# TimerSwitch.net
KiCad netlist of a schematic drawn in Altium Designer
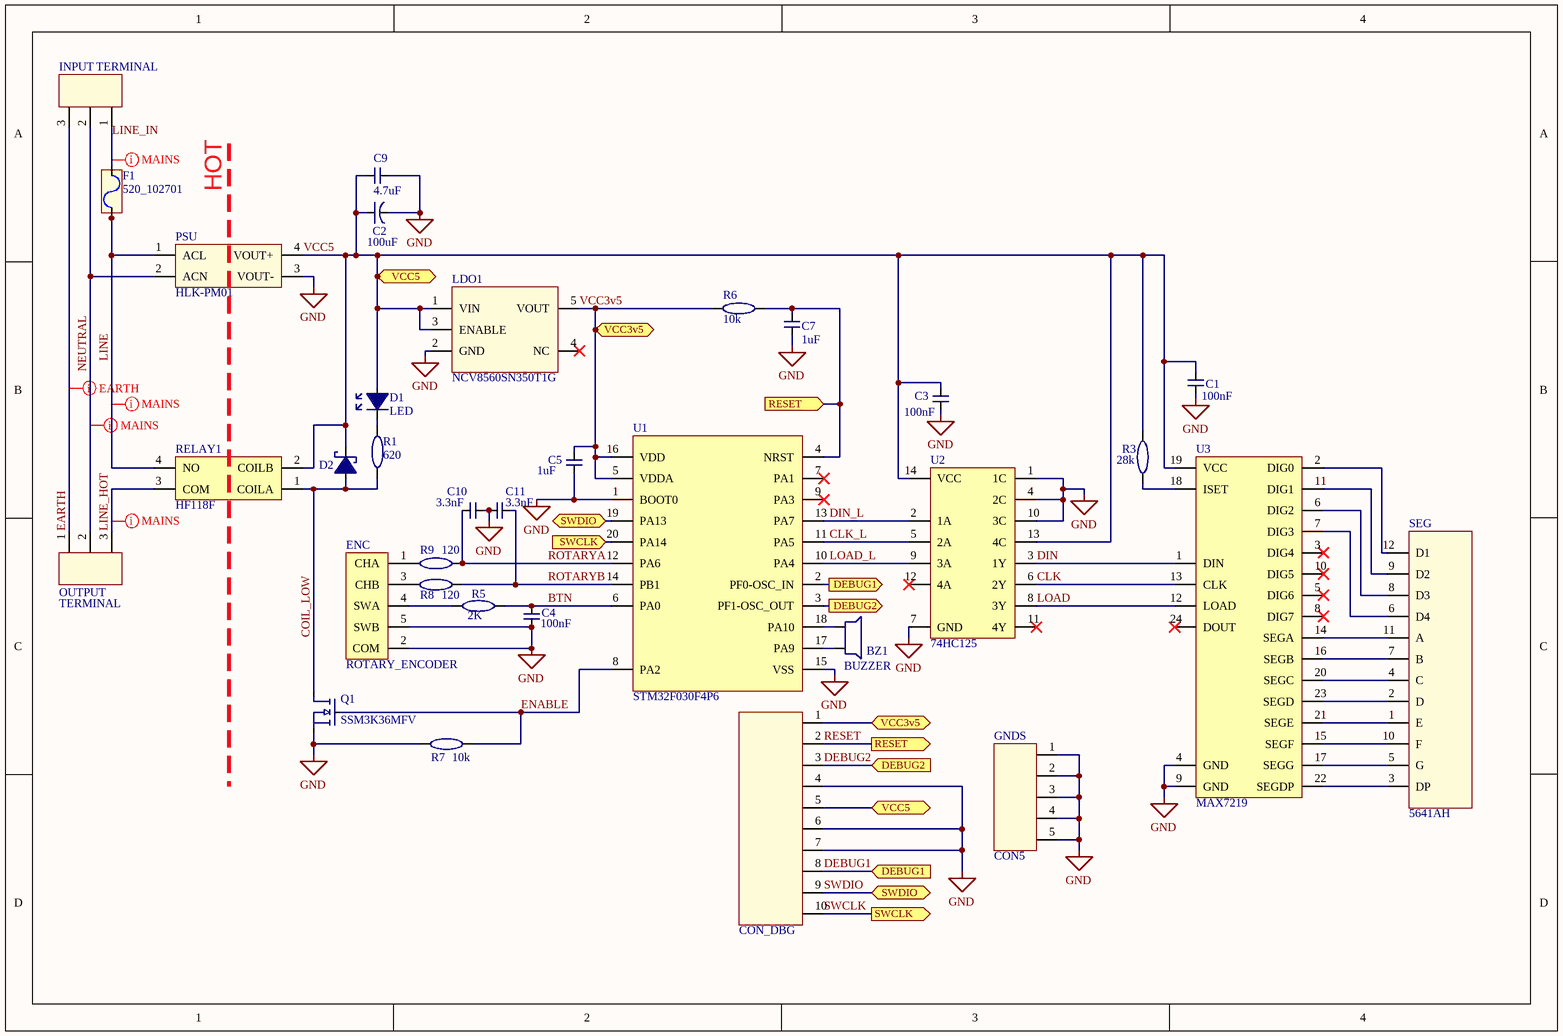
[diagram p0: TimerSwitch.SchDoc]

(export (version "E")
  (design (tool "Eeschema 10.0.6"))
  (components
    (comp (ref "BZ1")
      (value "BUZZER")
      (footprint "PIEZO_BUZZER")
      (libsource (lib "TimerSwitch") (part "BUZZER"))
    )
    (comp (ref "C1")
      (value "100nF")
      (footprint "CAPC1608X07L")
      (libsource (lib "TimerSwitch") (part "CAP_CERAMIC"))
    )
    (comp (ref "C2")
      (value "100uF")
      (footprint "CAPAE9585X105L")
      (libsource (lib "TimerSwitch") (part "CAP_ELECTROLYTIC"))
    )
    (comp (ref "C3")
      (value "100nF")
      (footprint "CAPC1608X07L")
      (libsource (lib "TimerSwitch") (part "CAP_CERAMIC"))
    )
    (comp (ref "C4")
      (value "100nF")
      (footprint "CAPC1608X07L")
      (libsource (lib "TimerSwitch") (part "CAP_CERAMIC"))
    )
    (comp (ref "C5")
      (value "1uF")
      (footprint "CAPC1608X07L")
      (libsource (lib "TimerSwitch") (part "CAP_CERAMIC"))
    )
    (comp (ref "C7")
      (value "1uF")
      (footprint "CAPC1608X07L")
      (libsource (lib "TimerSwitch") (part "CAP_CERAMIC"))
    )
    (comp (ref "C9")
      (value "4.7uF")
      (footprint "CAPC3216X07L")
      (description "Ceramic capacitor")
      (libsource (lib "TimerSwitch") (part "CAP_CERAMIC"))
    )
    (comp (ref "C10")
      (value "3.3nF")
      (footprint "CAPC1608X07L")
      (description "Ceramic capacitor")
      (libsource (lib "TimerSwitch") (part "CAP_CERAMIC"))
    )
    (comp (ref "C11")
      (value "3.3nF")
      (footprint "CAPC1608X07L")
      (description "Ceramic capacitor")
      (libsource (lib "TimerSwitch") (part "CAP_CERAMIC"))
    )
    (comp (ref "CON_DBG")
      (value "CON10")
      (footprint "CON10")
      (description "Debug connector")
      (libsource (lib "TimerSwitch") (part "CON10"))
    )
    (comp (ref "D1")
      (value "LED")
      (footprint "LED")
      (description "5mm through hole LED")
      (libsource (lib "TimerSwitch") (part "LED"))
    )
    (comp (ref "D2")
      (value "DSF05S30U")
      (footprint "SODFL250X100-2L")
      (description "Schottky Diode 20v 500mA")
      (libsource (lib "TimerSwitch") (part "DSF05S30U"))
    )
    (comp (ref "ENC")
      (value "ROTARY_ENCODER")
      (footprint "PEC12R-4XXXF-SXXXX_1")
      (description "Generic rotary encoder")
      (libsource (lib "TimerSwitch") (part "ROTARY_ENCODER"))
    )
    (comp (ref "F1")
      (value "520_102701")
      (footprint "5x20 FUSE")
      (description "5x20 5A fuse speed F")
      (libsource (lib "TimerSwitch") (part "520_102701"))
    )
    (comp (ref "GNDS") (value "CON5") (footprint "CON5") (libsource (lib "TimerSwitch") (part "CON5")))
    (comp (ref "INPUT")
      (value "TERMINAL")
      (footprint "TERMINAL_BLOCK")
      (description "3 way terminal block")
      (libsource (lib "") (part "TERMINAL_1"))
    )
    (comp (ref "LDO1")
      (value "NCV8560SN350T1G")
      (footprint "TSOP95P280X110-6L")
      (description "3.5V 150mA LDO")
      (libsource (lib "TimerSwitch") (part "NCV8560SN350T1G"))
    )
    (comp (ref "OUTPUT")
      (value "TERMINAL")
      (footprint "TERMINAL_BLOCK")
      (description "3 way terminal block")
      (libsource (lib "TimerSwitch") (part "TERMINAL"))
    )
    (comp (ref "PSU")
      (value "HLK-PM01")
      (footprint "HLK-PM01")
      (description "5V PSU 0.6A")
      (libsource (lib "TimerSwitch") (part "HLK-PM01"))
    )
    (comp (ref "Q1")
      (value "SSM3K36MFV")
      (footprint "SOT95P230X110-3L")
      (description "MOSFET N")
      (libsource (lib "TimerSwitch") (part "SSM3K36MFV"))
    )
    (comp (ref "R1")
      (value "620")
      (footprint "RESC1608X05L")
      (libsource (lib "TimerSwitch") (part "RESISTOR"))
    )
    (comp (ref "R3")
      (value "28k")
      (footprint "RESC1608X05L")
      (libsource (lib "TimerSwitch") (part "RESISTOR"))
    )
    (comp (ref "R5")
      (value "2K")
      (footprint "RESC1608X05L")
      (libsource (lib "TimerSwitch") (part "RESISTOR"))
    )
    (comp (ref "R6")
      (value "10k")
      (footprint "RESC1608X05L")
      (libsource (lib "TimerSwitch") (part "RESISTOR"))
    )
    (comp (ref "R7")
      (value "10k")
      (footprint "RESC1608X05L")
      (libsource (lib "TimerSwitch") (part "RESISTOR"))
    )
    (comp (ref "R8")
      (value "120")
      (footprint "RESC1608X05L")
      (description "Resistor 1%")
      (libsource (lib "TimerSwitch") (part "RESISTOR"))
    )
    (comp (ref "R9")
      (value "120")
      (footprint "RESC1608X05L")
      (description "Resistor 1%")
      (libsource (lib "TimerSwitch") (part "RESISTOR"))
    )
    (comp (ref "RELAY1")
      (value "HF118F")
      (footprint "G5RL-1-E-HR")
      (description "240V 10A Relay 5V")
      (libsource (lib "TimerSwitch") (part "HF118F"))
    )
    (comp (ref "SEG")
      (value "5641AH")
      (footprint "5641AH")
      (description "7+1 x 4 Segment display")
      (libsource (lib "TimerSwitch") (part "5641AH"))
    )
    (comp (ref "U1")
      (value "STM32F030F4P6")
      (footprint "TSOP65P630X120-20L")
      (description "Microcontroller 4KB RAM 16KB Flash")
      (libsource (lib "TimerSwitch") (part "STM32F030F4P6"))
    )
    (comp (ref "U2")
      (value "74HC125")
      (footprint "SOIC127P600X175-14L")
      (description "4 Channel level shifter")
      (libsource (lib "TimerSwitch") (part "74HC125"))
    )
    (comp (ref "U3")
      (value "MAX7219")
      (footprint "SOIC127P1030X265-24L")
      (description "7 Segment LED Driver")
      (libsource (lib "TimerSwitch") (part "MAX7219"))
    )
  )
  (nets
    (net (code "1") (name "/BTN") (class "Default")
      (node (ref "C4") (pin "2") (pinfunction "B_2") (pintype "passive"))
      (node (ref "R5") (pin "1") (pinfunction "A_1") (pintype "passive"))
      (node (ref "U1") (pin "6") (pinfunction "PA0_6") (pintype "passive"))
    )
    (net (code "2") (name "/CLK") (class "Default")
      (node (ref "U2") (pin "6") (pinfunction "2Y_6") (pintype "passive"))
      (node (ref "U3") (pin "13") (pinfunction "CLK_13") (pintype "passive"))
    )
    (net (code "3") (name "/CLK_L") (class "Default")
      (node (ref "U1") (pin "11") (pinfunction "PA5_11") (pintype "passive"))
      (node (ref "U2") (pin "5") (pinfunction "2A_5") (pintype "passive"))
    )
    (net (code "4") (name "/COIL_LOW") (class "Default")
      (node (ref "D2") (pin "1") (pinfunction "A_1") (pintype "passive"))
      (node (ref "Q1") (pin "3") (pinfunction "D_3") (pintype "passive"))
      (node (ref "R1") (pin "1") (pinfunction "A_1") (pintype "passive"))
      (node (ref "RELAY1") (pin "1") (pinfunction "COILA_1") (pintype "passive"))
    )
    (net (code "5") (name "/DEBUG1") (class "Default")
      (node (ref "CON_DBG") (pin "8") (pinfunction "8_8") (pintype "passive"))
      (node (ref "U1") (pin "2") (pinfunction "PF0-OSC_IN_2") (pintype "passive"))
    )
    (net (code "6") (name "/DEBUG2") (class "Default")
      (node (ref "CON_DBG") (pin "3") (pintype "passive"))
      (node (ref "U1") (pin "3") (pinfunction "PF1-OSC_OUT_3") (pintype "passive"))
    )
    (net (code "7") (name "/DIN") (class "Default")
      (node (ref "U2") (pin "3") (pinfunction "1Y_3") (pintype "passive"))
      (node (ref "U3") (pin "1") (pinfunction "DIN_1") (pintype "passive"))
    )
    (net (code "8") (name "/DIN_L") (class "Default")
      (node (ref "U1") (pin "13") (pinfunction "PA7_13") (pintype "passive"))
      (node (ref "U2") (pin "2") (pinfunction "1A_2") (pintype "passive"))
    )
    (net (code "9") (name "/EARTH") (class "Default")
      (node (ref "INPUT") (pin "3") (pinfunction "3_3") (pintype "passive"))
      (node (ref "OUTPUT") (pin "1") (pinfunction "1_1") (pintype "passive"))
    )
    (net (code "10") (name "/ENABLE") (class "Default")
      (node (ref "Q1") (pin "1") (pinfunction "G_1") (pintype "passive"))
      (node (ref "R7") (pin "2") (pinfunction "B_2") (pintype "passive"))
      (node (ref "U1") (pin "8") (pinfunction "PA2_8") (pintype "passive"))
    )
    (net (code "11") (name "/LINE") (class "Default")
      (node (ref "F1") (pin "2") (pinfunction "2_2") (pintype "passive"))
      (node (ref "PSU") (pin "1") (pinfunction "ACL_1") (pintype "passive"))
      (node (ref "RELAY1") (pin "4") (pinfunction "NO_4") (pintype "passive"))
    )
    (net (code "12") (name "/LINE_HOT") (class "Default")
      (node (ref "OUTPUT") (pin "3") (pinfunction "3_3") (pintype "passive"))
      (node (ref "RELAY1") (pin "3") (pinfunction "COM_3") (pintype "passive"))
    )
    (net (code "13") (name "/LINE_IN") (class "Default")
      (node (ref "F1") (pin "1") (pinfunction "1_1") (pintype "passive"))
      (node (ref "INPUT") (pin "1") (pinfunction "1_1") (pintype "passive"))
    )
    (net (code "14") (name "/LOAD") (class "Default")
      (node (ref "U2") (pin "8") (pinfunction "3Y_8") (pintype "passive"))
      (node (ref "U3") (pin "12") (pinfunction "LOAD_12") (pintype "passive"))
    )
    (net (code "15") (name "/LOAD_L") (class "Default")
      (node (ref "U1") (pin "10") (pinfunction "PA4_10") (pintype "passive"))
      (node (ref "U2") (pin "9") (pinfunction "3A_9") (pintype "passive"))
    )
    (net (code "16") (name "/NEUTRAL") (class "Default")
      (node (ref "INPUT") (pin "2") (pinfunction "2_2") (pintype "passive"))
      (node (ref "OUTPUT") (pin "2") (pinfunction "2_2") (pintype "passive"))
      (node (ref "PSU") (pin "2") (pinfunction "ACN_2") (pintype "passive"))
    )
    (net (code "17") (name "/RESET") (class "Default")
      (node (ref "C7") (pin "2") (pinfunction "B_2") (pintype "passive"))
      (node (ref "CON_DBG") (pin "2") (pintype "passive"))
      (node (ref "R6") (pin "1") (pinfunction "A_1") (pintype "passive"))
      (node (ref "U1") (pin "4") (pinfunction "NRST_4") (pintype "passive"))
    )
    (net (code "18") (name "/ROTARYA") (class "Default")
      (node (ref "C10") (pin "1") (pinfunction "A_1") (pintype "passive"))
      (node (ref "R9") (pin "2") (pinfunction "B_2") (pintype "passive"))
      (node (ref "U1") (pin "12") (pinfunction "PA6_12") (pintype "passive"))
    )
    (net (code "19") (name "/ROTARYB") (class "Default")
      (node (ref "C11") (pin "2") (pinfunction "B_2") (pintype "passive"))
      (node (ref "R8") (pin "2") (pinfunction "B_2") (pintype "passive"))
      (node (ref "U1") (pin "14") (pinfunction "PB1_14") (pintype "passive"))
    )
    (net (code "20") (name "/SWCLK") (class "Default")
      (node (ref "CON_DBG") (pin "10") (pinfunction "10_10") (pintype "passive"))
      (node (ref "U1") (pin "20") (pinfunction "PA14_20") (pintype "passive"))
    )
    (net (code "21") (name "/SWDIO") (class "Default")
      (node (ref "CON_DBG") (pin "9") (pinfunction "9_9") (pintype "passive"))
      (node (ref "U1") (pin "19") (pinfunction "PA13_19") (pintype "passive"))
    )
    (net (code "22") (name "/VCC3v5") (class "Default")
      (node (ref "C5") (pin "1") (pinfunction "A_1") (pintype "passive"))
      (node (ref "CON_DBG") (pin "1") (pintype "passive"))
      (node (ref "LDO1") (pin "5") (pinfunction "VOUT_5") (pintype "passive"))
      (node (ref "R6") (pin "2") (pinfunction "B_2") (pintype "passive"))
      (node (ref "U1") (pin "16") (pinfunction "VDD_16") (pintype "passive"))
      (node (ref "U1") (pin "5") (pinfunction "VDDA_5") (pintype "passive"))
    )
    (net (code "23") (name "/VCC5") (class "Default")
      (node (ref "C1") (pin "2") (pinfunction "B_2") (pintype "passive"))
      (node (ref "C2") (pin "1") (pinfunction "A_1") (pintype "passive"))
      (node (ref "C3") (pin "2") (pinfunction "B_2") (pintype "passive"))
      (node (ref "C9") (pin "1") (pinfunction "A_1") (pintype "passive"))
      (node (ref "CON_DBG") (pin "5") (pintype "passive"))
      (node (ref "D1") (pin "1") (pinfunction "A_1") (pintype "passive"))
      (node (ref "D2") (pin "2") (pinfunction "C_2") (pintype "passive"))
      (node (ref "LDO1") (pin "1") (pinfunction "VIN_1") (pintype "passive"))
      (node (ref "LDO1") (pin "3") (pinfunction "ENABLE_3") (pintype "passive"))
      (node (ref "PSU") (pin "4") (pinfunction "VOUT+_4") (pintype "passive"))
      (node (ref "R3") (pin "2") (pinfunction "B_2") (pintype "passive"))
      (node (ref "RELAY1") (pin "2") (pinfunction "COILB_2") (pintype "passive"))
      (node (ref "U2") (pin "13") (pinfunction "4C_13") (pintype "passive"))
      (node (ref "U2") (pin "14") (pinfunction "VCC_14") (pintype "passive"))
      (node (ref "U3") (pin "19") (pinfunction "VCC_19") (pintype "passive"))
    )
    (net (code "24") (name "GND") (class "Default")
      (node (ref "C1") (pin "1") (pinfunction "A_1") (pintype "passive"))
      (node (ref "C10") (pin "2") (pinfunction "B_2") (pintype "passive"))
      (node (ref "C11") (pin "1") (pinfunction "A_1") (pintype "passive"))
      (node (ref "C2") (pin "2") (pinfunction "C_2") (pintype "passive"))
      (node (ref "C3") (pin "1") (pinfunction "A_1") (pintype "passive"))
      (node (ref "C4") (pin "1") (pinfunction "A_1") (pintype "passive"))
      (node (ref "C5") (pin "2") (pinfunction "B_2") (pintype "passive"))
      (node (ref "C7") (pin "1") (pinfunction "A_1") (pintype "passive"))
      (node (ref "C9") (pin "2") (pinfunction "B_2") (pintype "passive"))
      (node (ref "CON_DBG") (pin "4") (pintype "passive"))
      (node (ref "CON_DBG") (pin "6") (pintype "passive"))
      (node (ref "CON_DBG") (pin "7") (pinfunction "7_7") (pintype "passive"))
      (node (ref "ENC") (pin "2") (pinfunction "COM_2") (pintype "passive"))
      (node (ref "ENC") (pin "5") (pinfunction "SWB_5") (pintype "passive"))
      (node (ref "GNDS") (pin "1") (pinfunction "1_1") (pintype "passive"))
      (node (ref "GNDS") (pin "2") (pinfunction "2_2") (pintype "passive"))
      (node (ref "GNDS") (pin "3") (pinfunction "3_3") (pintype "passive"))
      (node (ref "GNDS") (pin "4") (pinfunction "4_4") (pintype "passive"))
      (node (ref "GNDS") (pin "5") (pinfunction "5_5") (pintype "passive"))
      (node (ref "LDO1") (pin "2") (pinfunction "GND_2") (pintype "passive"))
      (node (ref "PSU") (pin "3") (pinfunction "VOUT-_3") (pintype "passive"))
      (node (ref "Q1") (pin "2") (pinfunction "S_2") (pintype "passive"))
      (node (ref "R7") (pin "1") (pinfunction "A_1") (pintype "passive"))
      (node (ref "U1") (pin "1") (pinfunction "BOOT0_1") (pintype "passive"))
      (node (ref "U1") (pin "15") (pinfunction "VSS_15") (pintype "passive"))
      (node (ref "U2") (pin "1") (pinfunction "1C_1") (pintype "passive"))
      (node (ref "U2") (pin "10") (pinfunction "3C_10") (pintype "passive"))
      (node (ref "U2") (pin "4") (pinfunction "2C_4") (pintype "passive"))
      (node (ref "U2") (pin "7") (pinfunction "GND_7") (pintype "passive"))
      (node (ref "U3") (pin "4") (pinfunction "GND_4") (pintype "passive"))
      (node (ref "U3") (pin "9") (pinfunction "GND_9") (pintype "passive"))
    )
    (net (code "25") (name "Net-(D1-C)") (class "Default")
      (node (ref "D1") (pin "2") (pinfunction "C_2") (pintype "passive"))
      (node (ref "R1") (pin "2") (pinfunction "B_2") (pintype "passive"))
    )
    (net (code "26") (name "Net-(ENC-CHA)") (class "Default")
      (node (ref "ENC") (pin "1") (pinfunction "CHA_1") (pintype "passive"))
      (node (ref "R9") (pin "1") (pinfunction "A_1") (pintype "passive"))
    )
    (net (code "27") (name "Net-(ENC-CHB)") (class "Default")
      (node (ref "ENC") (pin "3") (pinfunction "CHB_3") (pintype "passive"))
      (node (ref "R8") (pin "1") (pinfunction "A_1") (pintype "passive"))
    )
    (net (code "28") (name "Net-(ENC-SWA)") (class "Default")
      (node (ref "ENC") (pin "4") (pinfunction "SWA_4") (pintype "passive"))
      (node (ref "R5") (pin "2") (pinfunction "B_2") (pintype "passive"))
    )
    (net (code "29") (name "Net-(R3-A)") (class "Default")
      (node (ref "R3") (pin "1") (pinfunction "A_1") (pintype "passive"))
      (node (ref "U3") (pin "18") (pinfunction "ISET_18") (pintype "passive"))
    )
    (net (code "30") (name "Net-(SEG-A)") (class "Default")
      (node (ref "SEG") (pin "11") (pinfunction "A_11") (pintype "passive"))
      (node (ref "U3") (pin "14") (pinfunction "SEGA_14") (pintype "passive"))
    )
    (net (code "31") (name "Net-(SEG-B)") (class "Default")
      (node (ref "SEG") (pin "7") (pinfunction "B_7") (pintype "passive"))
      (node (ref "U3") (pin "16") (pinfunction "SEGB_16") (pintype "passive"))
    )
    (net (code "32") (name "Net-(SEG-C)") (class "Default")
      (node (ref "SEG") (pin "4") (pinfunction "C_4") (pintype "passive"))
      (node (ref "U3") (pin "20") (pinfunction "SEGC_20") (pintype "passive"))
    )
    (net (code "33") (name "Net-(SEG-D)") (class "Default")
      (node (ref "SEG") (pin "2") (pinfunction "D_2") (pintype "passive"))
      (node (ref "U3") (pin "23") (pinfunction "SEGD_23") (pintype "passive"))
    )
    (net (code "34") (name "Net-(SEG-D1)") (class "Default")
      (node (ref "SEG") (pin "12") (pinfunction "D1_12") (pintype "passive"))
      (node (ref "U3") (pin "2") (pinfunction "DIG0_2") (pintype "passive"))
    )
    (net (code "35") (name "Net-(SEG-D2)") (class "Default")
      (node (ref "SEG") (pin "9") (pinfunction "D2_9") (pintype "passive"))
      (node (ref "U3") (pin "11") (pinfunction "DIG1_11") (pintype "passive"))
    )
    (net (code "36") (name "Net-(SEG-D3)") (class "Default")
      (node (ref "SEG") (pin "8") (pinfunction "D3_8") (pintype "passive"))
      (node (ref "U3") (pin "6") (pinfunction "DIG2_6") (pintype "passive"))
    )
    (net (code "37") (name "Net-(SEG-D4)") (class "Default")
      (node (ref "SEG") (pin "6") (pinfunction "D4_6") (pintype "passive"))
      (node (ref "U3") (pin "7") (pinfunction "DIG3_7") (pintype "passive"))
    )
    (net (code "38") (name "Net-(SEG-DP)") (class "Default")
      (node (ref "SEG") (pin "3") (pinfunction "DP_3") (pintype "passive"))
      (node (ref "U3") (pin "22") (pinfunction "SEGDP_22") (pintype "passive"))
    )
    (net (code "39") (name "Net-(SEG-E)") (class "Default")
      (node (ref "SEG") (pin "1") (pinfunction "E_1") (pintype "passive"))
      (node (ref "U3") (pin "21") (pinfunction "SEGE_21") (pintype "passive"))
    )
    (net (code "40") (name "Net-(SEG-F)") (class "Default")
      (node (ref "SEG") (pin "10") (pinfunction "F_10") (pintype "passive"))
      (node (ref "U3") (pin "15") (pinfunction "SEGF_15") (pintype "passive"))
    )
    (net (code "41") (name "Net-(SEG-G)") (class "Default")
      (node (ref "SEG") (pin "5") (pinfunction "G_5") (pintype "passive"))
      (node (ref "U3") (pin "17") (pinfunction "SEGG_17") (pintype "passive"))
    )
    (net (code "42") (name "Net-(U1-PA9)") (class "Default")
      (node (ref "BZ1") (pin "2") (pinfunction "2_2") (pintype "passive"))
      (node (ref "U1") (pin "17") (pinfunction "PA9_17") (pintype "passive"))
    )
    (net (code "43") (name "Net-(U1-PA10)") (class "Default")
      (node (ref "BZ1") (pin "1") (pinfunction "1_1") (pintype "passive"))
      (node (ref "U1") (pin "18") (pinfunction "PA10_18") (pintype "passive"))
    )
    (net (code "44") (name "unconnected-(LDO1-NC-Pad4)") (class "Default")
      (node (ref "LDO1") (pin "4") (pinfunction "NC_4") (pintype "passive+no_connect"))
    )
    (net (code "45") (name "unconnected-(U1-PA1-Pad7)") (class "Default")
      (node (ref "U1") (pin "7") (pinfunction "PA1_7") (pintype "passive+no_connect"))
    )
    (net (code "46") (name "unconnected-(U1-PA3-Pad9)") (class "Default")
      (node (ref "U1") (pin "9") (pinfunction "PA3_9") (pintype "passive+no_connect"))
    )
    (net (code "47") (name "unconnected-(U2-4A-Pad12)") (class "Default")
      (node (ref "U2") (pin "12") (pinfunction "4A_12") (pintype "passive+no_connect"))
    )
    (net (code "48") (name "unconnected-(U2-4Y-Pad11)") (class "Default")
      (node (ref "U2") (pin "11") (pinfunction "4Y_11") (pintype "passive+no_connect"))
    )
    (net (code "49") (name "unconnected-(U3-DIG4-Pad3)") (class "Default")
      (node (ref "U3") (pin "3") (pinfunction "DIG4_3") (pintype "passive+no_connect"))
    )
    (net (code "50") (name "unconnected-(U3-DIG5-Pad10)") (class "Default")
      (node (ref "U3") (pin "10") (pinfunction "DIG5_10") (pintype "passive+no_connect"))
    )
    (net (code "51") (name "unconnected-(U3-DIG6-Pad5)") (class "Default")
      (node (ref "U3") (pin "5") (pinfunction "DIG6_5") (pintype "passive+no_connect"))
    )
    (net (code "52") (name "unconnected-(U3-DIG7-Pad8)") (class "Default")
      (node (ref "U3") (pin "8") (pinfunction "DIG7_8") (pintype "passive+no_connect"))
    )
    (net (code "53") (name "unconnected-(U3-DOUT-Pad24)") (class "Default")
      (node (ref "U3") (pin "24") (pinfunction "DOUT_24") (pintype "passive+no_connect"))
    )
  )
)
